# CAMAC.net
KiCad netlist of a schematic drawn in Altium Designer
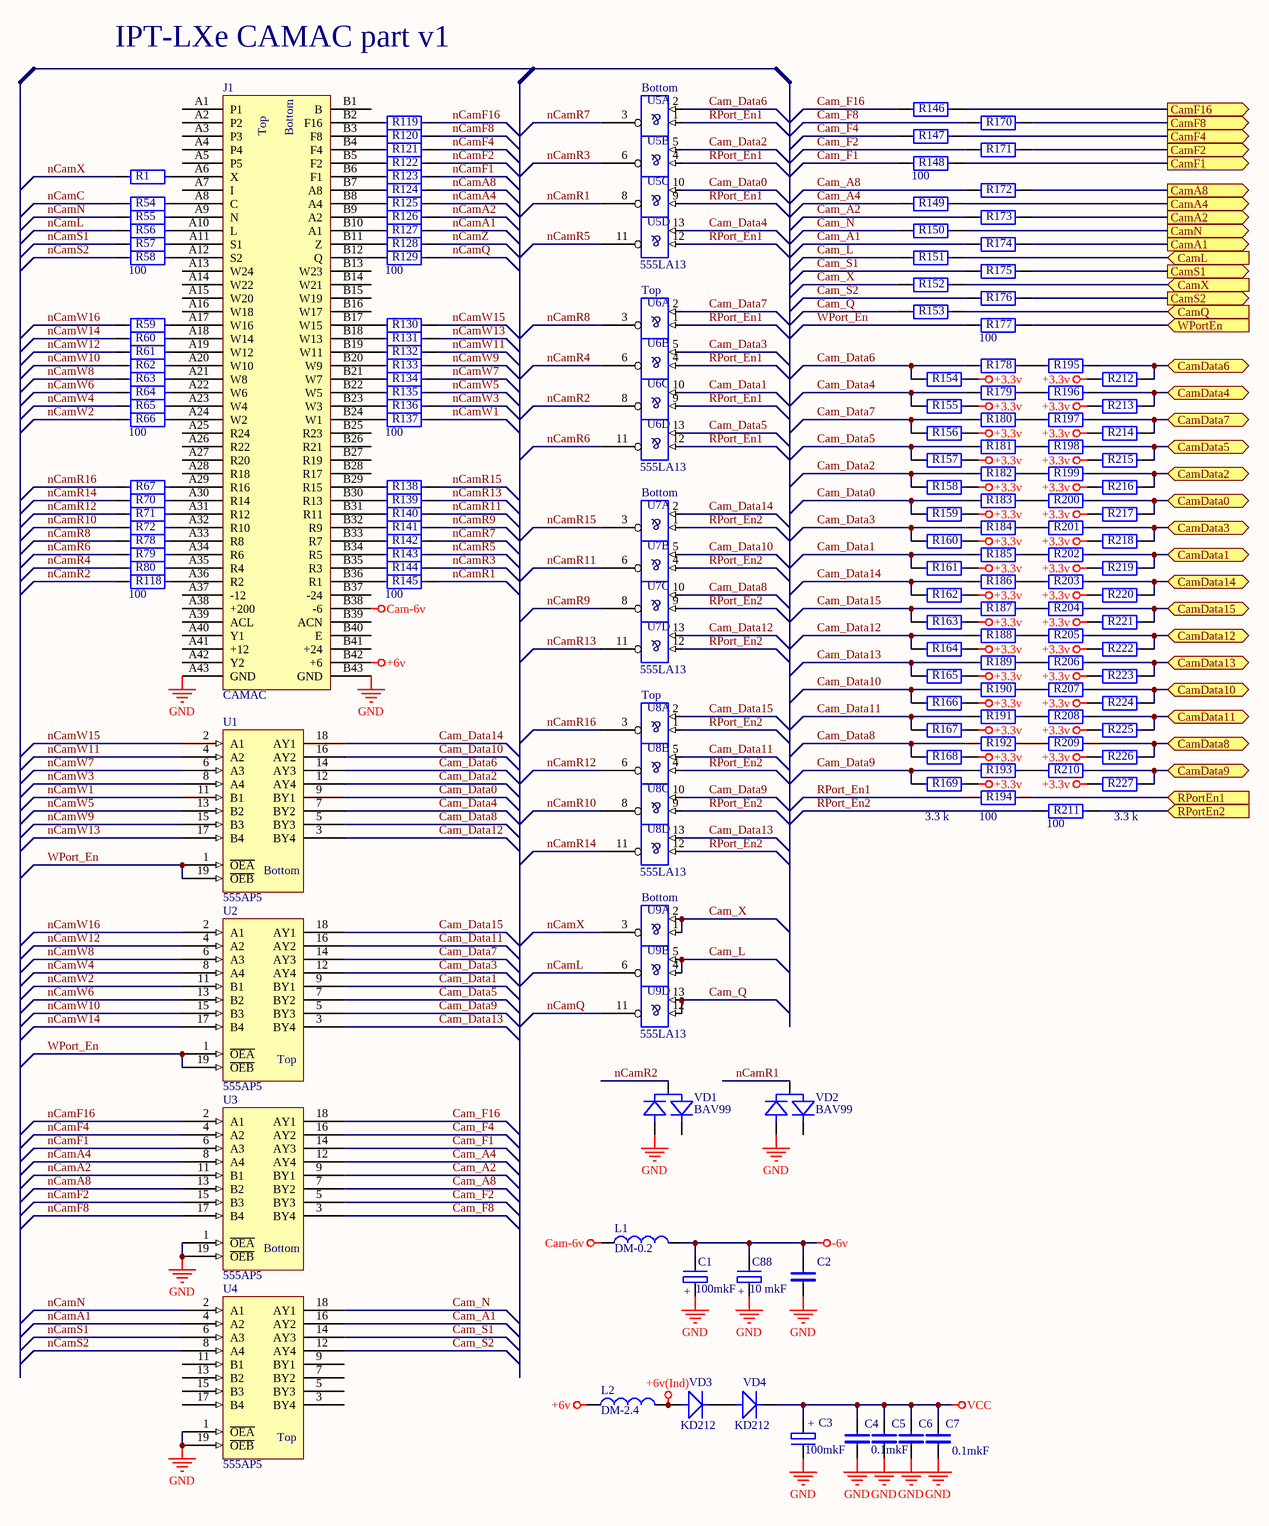
[diagram p0: CAMAC.SchDoc]

(export (version "E")
  (design (tool "Eeschema 10.0.6"))
  (components
    (comp (ref "C1") (value "100mkF") (footprint "CP7343") (libsource (lib "*") (part "C POL")))
    (comp (ref "C2") (value "0.1mkF") (footprint "chip1206") (libsource (lib "vDevice") (part "C")))
    (comp (ref "C3") (value "100mkF") (footprint "CP7343") (libsource (lib "*") (part "C POL")))
    (comp (ref "C4") (value "0.1mkF") (footprint "chip1206") (libsource (lib "vDevice") (part "C")))
    (comp (ref "C5") (value "0.1mkF") (footprint "chip1206") (libsource (lib "vDevice") (part "C")))
    (comp (ref "C6") (value "0.1mkF") (footprint "chip1206") (libsource (lib "vDevice") (part "C")))
    (comp (ref "C7") (value "0.1mkF") (footprint "chip1206") (libsource (lib "vDevice") (part "C")))
    (comp (ref "C88") (value "10 mkF") (footprint "CP6032") (libsource (lib "*") (part "C POL")))
    (comp (ref "J1") (value "CAMAC") (footprint "CAMAC") (libsource (lib "*") (part "CAMACF")))
    (comp (ref "L1") (value "DM-0.2") (footprint "INDUCT2") (libsource (lib "*") (part "INDUCTOR")))
    (comp (ref "L2") (value "DM-2.4") (footprint "INDUCT2") (libsource (lib "*") (part "INDUCTOR")))
    (comp (ref "R1") (value "100") (footprint "chip0805") (libsource (lib "vDevice") (part "R")))
    (comp (ref "R54") (value "100") (footprint "chip0805") (libsource (lib "vDevice") (part "R")))
    (comp (ref "R55") (value "100") (footprint "chip0805") (libsource (lib "vDevice") (part "R")))
    (comp (ref "R56") (value "100") (footprint "chip0805") (libsource (lib "vDevice") (part "R")))
    (comp (ref "R57") (value "100") (footprint "chip0805") (libsource (lib "vDevice") (part "R")))
    (comp (ref "R58") (value "100") (footprint "chip0805") (libsource (lib "vDevice") (part "R")))
    (comp (ref "R59") (value "100") (footprint "chip0805") (libsource (lib "vDevice") (part "R")))
    (comp (ref "R60") (value "100") (footprint "chip0805") (libsource (lib "vDevice") (part "R")))
    (comp (ref "R61") (value "100") (footprint "chip0805") (libsource (lib "vDevice") (part "R")))
    (comp (ref "R62") (value "100") (footprint "chip0805") (libsource (lib "vDevice") (part "R")))
    (comp (ref "R63") (value "100") (footprint "chip0805") (libsource (lib "vDevice") (part "R")))
    (comp (ref "R64") (value "100") (footprint "chip0805") (libsource (lib "vDevice") (part "R")))
    (comp (ref "R65") (value "100") (footprint "chip0805") (libsource (lib "vDevice") (part "R")))
    (comp (ref "R66") (value "100") (footprint "chip0805") (libsource (lib "vDevice") (part "R")))
    (comp (ref "R67") (value "100") (footprint "chip0805") (libsource (lib "vDevice") (part "R")))
    (comp (ref "R70") (value "100") (footprint "chip0805") (libsource (lib "vDevice") (part "R")))
    (comp (ref "R71") (value "100") (footprint "chip0805") (libsource (lib "vDevice") (part "R")))
    (comp (ref "R72") (value "100") (footprint "chip0805") (libsource (lib "vDevice") (part "R")))
    (comp (ref "R78") (value "100") (footprint "chip0805") (libsource (lib "vDevice") (part "R")))
    (comp (ref "R79") (value "100") (footprint "chip0805") (libsource (lib "vDevice") (part "R")))
    (comp (ref "R80") (value "100") (footprint "chip0805") (libsource (lib "vDevice") (part "R")))
    (comp (ref "R118") (value "100") (footprint "chip0805") (libsource (lib "vDevice") (part "R")))
    (comp (ref "R119") (value "100") (footprint "chip0805") (libsource (lib "vDevice") (part "R")))
    (comp (ref "R120") (value "100") (footprint "chip0805") (libsource (lib "vDevice") (part "R")))
    (comp (ref "R121") (value "100") (footprint "chip0805") (libsource (lib "vDevice") (part "R")))
    (comp (ref "R122") (value "100") (footprint "chip0805") (libsource (lib "vDevice") (part "R")))
    (comp (ref "R123") (value "100") (footprint "chip0805") (libsource (lib "vDevice") (part "R")))
    (comp (ref "R124") (value "100") (footprint "chip0805") (libsource (lib "vDevice") (part "R")))
    (comp (ref "R125") (value "100") (footprint "chip0805") (libsource (lib "vDevice") (part "R")))
    (comp (ref "R126") (value "100") (footprint "chip0805") (libsource (lib "vDevice") (part "R")))
    (comp (ref "R127") (value "100") (footprint "chip0805") (libsource (lib "vDevice") (part "R")))
    (comp (ref "R128") (value "100") (footprint "chip0805") (libsource (lib "vDevice") (part "R")))
    (comp (ref "R129") (value "100") (footprint "chip0805") (libsource (lib "vDevice") (part "R")))
    (comp (ref "R130") (value "100") (footprint "chip0805") (libsource (lib "vDevice") (part "R")))
    (comp (ref "R131") (value "100") (footprint "chip0805") (libsource (lib "vDevice") (part "R")))
    (comp (ref "R132") (value "100") (footprint "chip0805") (libsource (lib "vDevice") (part "R")))
    (comp (ref "R133") (value "100") (footprint "chip0805") (libsource (lib "vDevice") (part "R")))
    (comp (ref "R134") (value "100") (footprint "chip0805") (libsource (lib "vDevice") (part "R")))
    (comp (ref "R135") (value "100") (footprint "chip0805") (libsource (lib "vDevice") (part "R")))
    (comp (ref "R136") (value "100") (footprint "chip0805") (libsource (lib "vDevice") (part "R")))
    (comp (ref "R137") (value "100") (footprint "chip0805") (libsource (lib "vDevice") (part "R")))
    (comp (ref "R138") (value "100") (footprint "chip0805") (libsource (lib "vDevice") (part "R")))
    (comp (ref "R139") (value "100") (footprint "chip0805") (libsource (lib "vDevice") (part "R")))
    (comp (ref "R140") (value "100") (footprint "chip0805") (libsource (lib "vDevice") (part "R")))
    (comp (ref "R141") (value "100") (footprint "chip0805") (libsource (lib "vDevice") (part "R")))
    (comp (ref "R142") (value "100") (footprint "chip0805") (libsource (lib "vDevice") (part "R")))
    (comp (ref "R143") (value "100") (footprint "chip0805") (libsource (lib "vDevice") (part "R")))
    (comp (ref "R144") (value "100") (footprint "chip0805") (libsource (lib "vDevice") (part "R")))
    (comp (ref "R145") (value "100") (footprint "chip0805") (libsource (lib "vDevice") (part "R")))
    (comp (ref "R146") (value "100") (footprint "chip0805") (libsource (lib "vDevice") (part "R")))
    (comp (ref "R147") (value "100") (footprint "chip0805") (libsource (lib "vDevice") (part "R")))
    (comp (ref "R148") (value "100") (footprint "chip0805") (libsource (lib "vDevice") (part "R")))
    (comp (ref "R149") (value "100") (footprint "chip0805") (libsource (lib "vDevice") (part "R")))
    (comp (ref "R150") (value "100") (footprint "chip0805") (libsource (lib "vDevice") (part "R")))
    (comp (ref "R151") (value "100") (footprint "chip0805") (libsource (lib "vDevice") (part "R")))
    (comp (ref "R152") (value "100") (footprint "chip0805") (libsource (lib "vDevice") (part "R")))
    (comp (ref "R153") (value "100") (footprint "chip0805") (libsource (lib "vDevice") (part "R")))
    (comp (ref "R154") (value "3.3 k") (footprint "chip0805") (libsource (lib "vDevice") (part "R")))
    (comp (ref "R155") (value "3.3 k") (footprint "chip0805") (libsource (lib "vDevice") (part "R")))
    (comp (ref "R156") (value "3.3 k") (footprint "chip0805") (libsource (lib "vDevice") (part "R")))
    (comp (ref "R157") (value "3.3 k") (footprint "chip0805") (libsource (lib "vDevice") (part "R")))
    (comp (ref "R158") (value "3.3 k") (footprint "chip0805") (libsource (lib "vDevice") (part "R")))
    (comp (ref "R159") (value "3.3 k") (footprint "chip0805") (libsource (lib "vDevice") (part "R")))
    (comp (ref "R160") (value "3.3 k") (footprint "chip0805") (libsource (lib "vDevice") (part "R")))
    (comp (ref "R161") (value "3.3 k") (footprint "chip0805") (libsource (lib "vDevice") (part "R")))
    (comp (ref "R162") (value "3.3 k") (footprint "chip0805") (libsource (lib "vDevice") (part "R")))
    (comp (ref "R163") (value "3.3 k") (footprint "chip0805") (libsource (lib "vDevice") (part "R")))
    (comp (ref "R164") (value "3.3 k") (footprint "chip0805") (libsource (lib "vDevice") (part "R")))
    (comp (ref "R165") (value "3.3 k") (footprint "chip0805") (libsource (lib "vDevice") (part "R")))
    (comp (ref "R166") (value "3.3 k") (footprint "chip0805") (libsource (lib "vDevice") (part "R")))
    (comp (ref "R167") (value "3.3 k") (footprint "chip0805") (libsource (lib "vDevice") (part "R")))
    (comp (ref "R168") (value "3.3 k") (footprint "chip0805") (libsource (lib "vDevice") (part "R")))
    (comp (ref "R169") (value "3.3 k") (footprint "chip0805") (libsource (lib "vDevice") (part "R")))
    (comp (ref "R170") (value "100") (footprint "chip0805") (libsource (lib "vDevice") (part "R")))
    (comp (ref "R171") (value "100") (footprint "chip0805") (libsource (lib "vDevice") (part "R")))
    (comp (ref "R172") (value "100") (footprint "chip0805") (libsource (lib "vDevice") (part "R")))
    (comp (ref "R173") (value "100") (footprint "chip0805") (libsource (lib "vDevice") (part "R")))
    (comp (ref "R174") (value "100") (footprint "chip0805") (libsource (lib "vDevice") (part "R")))
    (comp (ref "R175") (value "100") (footprint "chip0805") (libsource (lib "vDevice") (part "R")))
    (comp (ref "R176") (value "100") (footprint "chip0805") (libsource (lib "vDevice") (part "R")))
    (comp (ref "R177") (value "100") (footprint "chip0805") (libsource (lib "vDevice") (part "R")))
    (comp (ref "R178") (value "51") (footprint "chip0805") (libsource (lib "vDevice") (part "R")))
    (comp (ref "R179") (value "51") (footprint "chip0805") (libsource (lib "vDevice") (part "R")))
    (comp (ref "R180") (value "51") (footprint "chip0805") (libsource (lib "vDevice") (part "R")))
    (comp (ref "R181") (value "51") (footprint "chip0805") (libsource (lib "vDevice") (part "R")))
    (comp (ref "R182") (value "51") (footprint "chip0805") (libsource (lib "vDevice") (part "R")))
    (comp (ref "R183") (value "51") (footprint "chip0805") (libsource (lib "vDevice") (part "R")))
    (comp (ref "R184") (value "51") (footprint "chip0805") (libsource (lib "vDevice") (part "R")))
    (comp (ref "R185") (value "51") (footprint "chip0805") (libsource (lib "vDevice") (part "R")))
    (comp (ref "R186") (value "51") (footprint "chip0805") (libsource (lib "vDevice") (part "R")))
    (comp (ref "R187") (value "51") (footprint "chip0805") (libsource (lib "vDevice") (part "R")))
    (comp (ref "R188") (value "51") (footprint "chip0805") (libsource (lib "vDevice") (part "R")))
    (comp (ref "R189") (value "51") (footprint "chip0805") (libsource (lib "vDevice") (part "R")))
    (comp (ref "R190") (value "51") (footprint "chip0805") (libsource (lib "vDevice") (part "R")))
    (comp (ref "R191") (value "51") (footprint "chip0805") (libsource (lib "vDevice") (part "R")))
    (comp (ref "R192") (value "51") (footprint "chip0805") (libsource (lib "vDevice") (part "R")))
    (comp (ref "R193") (value "51") (footprint "chip0805") (libsource (lib "vDevice") (part "R")))
    (comp (ref "R194") (value "100") (footprint "chip0805") (libsource (lib "vDevice") (part "R")))
    (comp (ref "R195") (value "51") (footprint "chip0805") (libsource (lib "vDevice") (part "R")))
    (comp (ref "R196") (value "51") (footprint "chip0805") (libsource (lib "vDevice") (part "R")))
    (comp (ref "R197") (value "51") (footprint "chip0805") (libsource (lib "vDevice") (part "R")))
    (comp (ref "R198") (value "51") (footprint "chip0805") (libsource (lib "vDevice") (part "R")))
    (comp (ref "R199") (value "51") (footprint "chip0805") (libsource (lib "vDevice") (part "R")))
    (comp (ref "R200") (value "51") (footprint "chip0805") (libsource (lib "vDevice") (part "R")))
    (comp (ref "R201") (value "51") (footprint "chip0805") (libsource (lib "vDevice") (part "R")))
    (comp (ref "R202") (value "51") (footprint "chip0805") (libsource (lib "vDevice") (part "R")))
    (comp (ref "R203") (value "51") (footprint "chip0805") (libsource (lib "vDevice") (part "R")))
    (comp (ref "R204") (value "51") (footprint "chip0805") (libsource (lib "vDevice") (part "R")))
    (comp (ref "R205") (value "51") (footprint "chip0805") (libsource (lib "vDevice") (part "R")))
    (comp (ref "R206") (value "51") (footprint "chip0805") (libsource (lib "vDevice") (part "R")))
    (comp (ref "R207") (value "51") (footprint "chip0805") (libsource (lib "vDevice") (part "R")))
    (comp (ref "R208") (value "51") (footprint "chip0805") (libsource (lib "vDevice") (part "R")))
    (comp (ref "R209") (value "51") (footprint "chip0805") (libsource (lib "vDevice") (part "R")))
    (comp (ref "R210") (value "51") (footprint "chip0805") (libsource (lib "vDevice") (part "R")))
    (comp (ref "R211") (value "100") (footprint "chip0805") (libsource (lib "vDevice") (part "R")))
    (comp (ref "R212") (value "3.3 k") (footprint "chip0805") (libsource (lib "vDevice") (part "R")))
    (comp (ref "R213") (value "3.3 k") (footprint "chip0805") (libsource (lib "vDevice") (part "R")))
    (comp (ref "R214") (value "3.3 k") (footprint "chip0805") (libsource (lib "vDevice") (part "R")))
    (comp (ref "R215") (value "3.3 k") (footprint "chip0805") (libsource (lib "vDevice") (part "R")))
    (comp (ref "R216") (value "3.3 k") (footprint "chip0805") (libsource (lib "vDevice") (part "R")))
    (comp (ref "R217") (value "3.3 k") (footprint "chip0805") (libsource (lib "vDevice") (part "R")))
    (comp (ref "R218") (value "3.3 k") (footprint "chip0805") (libsource (lib "vDevice") (part "R")))
    (comp (ref "R219") (value "3.3 k") (footprint "chip0805") (libsource (lib "vDevice") (part "R")))
    (comp (ref "R220") (value "3.3 k") (footprint "chip0805") (libsource (lib "vDevice") (part "R")))
    (comp (ref "R221") (value "3.3 k") (footprint "chip0805") (libsource (lib "vDevice") (part "R")))
    (comp (ref "R222") (value "3.3 k") (footprint "chip0805") (libsource (lib "vDevice") (part "R")))
    (comp (ref "R223") (value "3.3 k") (footprint "chip0805") (libsource (lib "vDevice") (part "R")))
    (comp (ref "R224") (value "3.3 k") (footprint "chip0805") (libsource (lib "vDevice") (part "R")))
    (comp (ref "R225") (value "3.3 k") (footprint "chip0805") (libsource (lib "vDevice") (part "R")))
    (comp (ref "R226") (value "3.3 k") (footprint "chip0805") (libsource (lib "vDevice") (part "R")))
    (comp (ref "R227") (value "3.3 k") (footprint "chip0805") (libsource (lib "vDevice") (part "R")))
    (comp (ref "U1") (value "555AP5") (libsource (lib "vTTL") (part "555AP5")))
    (comp (ref "U2") (value "555AP5") (libsource (lib "vTTL") (part "555AP5")))
    (comp (ref "U3") (value "555AP5") (libsource (lib "vTTL") (part "555AP5")))
    (comp (ref "U4") (value "555AP5") (libsource (lib "vTTL") (part "555AP5")))
    (comp (ref "U5") (value "555LA13") (footprint "14DIP300") (libsource (lib "vTTL") (part "555LA13")))
    (comp (ref "U6") (value "555LA13") (footprint "14DIP300") (libsource (lib "vTTL") (part "555LA13")))
    (comp (ref "U7") (value "555LA13") (footprint "14DIP300") (libsource (lib "vTTL") (part "555LA13")))
    (comp (ref "U8") (value "555LA13") (footprint "14DIP300") (libsource (lib "vTTL") (part "555LA13")))
    (comp (ref "U9") (value "555LA13") (footprint "14DIP300") (libsource (lib "vTTL") (part "555LA13")))
    (comp (ref "VD1")
      (value "BAV99")
      (footprint "SOT-23")
      (description "Double diode")
      (libsource (lib "*") (part "BAV99"))
    )
    (comp (ref "VD2")
      (value "BAV99")
      (footprint "SOT-23")
      (description "Double diode")
      (libsource (lib "*") (part "BAV99"))
    )
    (comp (ref "VD3") (value "KD212") (footprint "DIODE6") (libsource (lib "*") (part "AD110")))
    (comp (ref "VD4") (value "KD212") (footprint "DIODE6") (libsource (lib "*") (part "AD110")))
  )
  (nets
    (net (code "1") (name "+3.3v") (class "Default")
      (node (ref "R154") (pin "2") (pinfunction "2_2") (pintype "passive"))
      (node (ref "R155") (pin "2") (pinfunction "2_2") (pintype "passive"))
      (node (ref "R156") (pin "2") (pinfunction "2_2") (pintype "passive"))
      (node (ref "R157") (pin "2") (pinfunction "2_2") (pintype "passive"))
      (node (ref "R158") (pin "2") (pinfunction "2_2") (pintype "passive"))
      (node (ref "R159") (pin "2") (pinfunction "2_2") (pintype "passive"))
      (node (ref "R160") (pin "2") (pinfunction "2_2") (pintype "passive"))
      (node (ref "R161") (pin "2") (pinfunction "2_2") (pintype "passive"))
      (node (ref "R162") (pin "2") (pinfunction "2_2") (pintype "passive"))
      (node (ref "R163") (pin "2") (pinfunction "2_2") (pintype "passive"))
      (node (ref "R164") (pin "2") (pinfunction "2_2") (pintype "passive"))
      (node (ref "R165") (pin "2") (pinfunction "2_2") (pintype "passive"))
      (node (ref "R166") (pin "2") (pinfunction "2_2") (pintype "passive"))
      (node (ref "R167") (pin "2") (pinfunction "2_2") (pintype "passive"))
      (node (ref "R168") (pin "2") (pinfunction "2_2") (pintype "passive"))
      (node (ref "R169") (pin "2") (pinfunction "2_2") (pintype "passive"))
      (node (ref "R212") (pin "1") (pinfunction "1_1") (pintype "passive"))
      (node (ref "R213") (pin "1") (pinfunction "1_1") (pintype "passive"))
      (node (ref "R214") (pin "1") (pinfunction "1_1") (pintype "passive"))
      (node (ref "R215") (pin "1") (pinfunction "1_1") (pintype "passive"))
      (node (ref "R216") (pin "1") (pinfunction "1_1") (pintype "passive"))
      (node (ref "R217") (pin "1") (pinfunction "1_1") (pintype "passive"))
      (node (ref "R218") (pin "1") (pinfunction "1_1") (pintype "passive"))
      (node (ref "R219") (pin "1") (pinfunction "1_1") (pintype "passive"))
      (node (ref "R220") (pin "1") (pinfunction "1_1") (pintype "passive"))
      (node (ref "R221") (pin "1") (pinfunction "1_1") (pintype "passive"))
      (node (ref "R222") (pin "1") (pinfunction "1_1") (pintype "passive"))
      (node (ref "R223") (pin "1") (pinfunction "1_1") (pintype "passive"))
      (node (ref "R224") (pin "1") (pinfunction "1_1") (pintype "passive"))
      (node (ref "R225") (pin "1") (pinfunction "1_1") (pintype "passive"))
      (node (ref "R226") (pin "1") (pinfunction "1_1") (pintype "passive"))
      (node (ref "R227") (pin "1") (pinfunction "1_1") (pintype "passive"))
    )
    (net (code "2") (name "+5V") (class "Default")
      (node (ref "U1") (pin "20") (pinfunction "+5V_20") (pintype "power_in"))
      (node (ref "U2") (pin "20") (pinfunction "+5V_20") (pintype "power_in"))
      (node (ref "U3") (pin "20") (pinfunction "+5V_20") (pintype "power_in"))
      (node (ref "U4") (pin "20") (pinfunction "+5V_20") (pintype "power_in"))
    )
    (net (code "3") (name "+6v") (class "Default")
      (node (ref "J1") (pin "B42") (pinfunction "+6_B42") (pintype "passive"))
      (node (ref "L2") (pin "1") (pinfunction "1_1") (pintype "passive"))
    )
    (net (code "4") (name "+6v(Ind)") (class "Default")
      (node (ref "L2") (pin "2") (pinfunction "2_2") (pintype "passive"))
      (node (ref "VD3") (pin "ANOD") (pinfunction "ANOD_ANOD") (pintype "passive"))
    )
    (net (code "5") (name "-6v") (class "Default")
      (node (ref "C1") (pin "-") (pinfunction "-_-") (pintype "passive"))
      (node (ref "C2") (pin "1") (pinfunction "1_1") (pintype "passive"))
      (node (ref "C88") (pin "-") (pinfunction "-_-") (pintype "passive"))
      (node (ref "L1") (pin "2") (pinfunction "2_2") (pintype "passive"))
    )
    (net (code "6") (name "/CamA1") (class "Default")
      (node (ref "R174") (pin "2") (pinfunction "2_2") (pintype "passive"))
    )
    (net (code "7") (name "/CamA2") (class "Default")
      (node (ref "R173") (pin "2") (pinfunction "2_2") (pintype "passive"))
    )
    (net (code "8") (name "/CamA4") (class "Default")
      (node (ref "R149") (pin "2") (pinfunction "2_2") (pintype "passive"))
    )
    (net (code "9") (name "/CamA8") (class "Default")
      (node (ref "R172") (pin "2") (pinfunction "2_2") (pintype "passive"))
    )
    (net (code "10") (name "/CamData0") (class "Default")
      (node (ref "R200") (pin "2") (pinfunction "2_2") (pintype "passive"))
      (node (ref "R217") (pin "2") (pinfunction "2_2") (pintype "passive"))
    )
    (net (code "11") (name "/CamData1") (class "Default")
      (node (ref "R202") (pin "2") (pinfunction "2_2") (pintype "passive"))
      (node (ref "R219") (pin "2") (pinfunction "2_2") (pintype "passive"))
    )
    (net (code "12") (name "/CamData2") (class "Default")
      (node (ref "R199") (pin "2") (pinfunction "2_2") (pintype "passive"))
      (node (ref "R216") (pin "2") (pinfunction "2_2") (pintype "passive"))
    )
    (net (code "13") (name "/CamData3") (class "Default")
      (node (ref "R201") (pin "2") (pinfunction "2_2") (pintype "passive"))
      (node (ref "R218") (pin "2") (pinfunction "2_2") (pintype "passive"))
    )
    (net (code "14") (name "/CamData4") (class "Default")
      (node (ref "R196") (pin "2") (pinfunction "2_2") (pintype "passive"))
      (node (ref "R213") (pin "2") (pinfunction "2_2") (pintype "passive"))
    )
    (net (code "15") (name "/CamData5") (class "Default")
      (node (ref "R198") (pin "2") (pinfunction "2_2") (pintype "passive"))
      (node (ref "R215") (pin "2") (pinfunction "2_2") (pintype "passive"))
    )
    (net (code "16") (name "/CamData6") (class "Default")
      (node (ref "R195") (pin "2") (pinfunction "2_2") (pintype "passive"))
      (node (ref "R212") (pin "2") (pinfunction "2_2") (pintype "passive"))
    )
    (net (code "17") (name "/CamData7") (class "Default")
      (node (ref "R197") (pin "2") (pinfunction "2_2") (pintype "passive"))
      (node (ref "R214") (pin "2") (pinfunction "2_2") (pintype "passive"))
    )
    (net (code "18") (name "/CamData8") (class "Default")
      (node (ref "R209") (pin "2") (pinfunction "2_2") (pintype "passive"))
      (node (ref "R226") (pin "2") (pinfunction "2_2") (pintype "passive"))
    )
    (net (code "19") (name "/CamData9") (class "Default")
      (node (ref "R210") (pin "2") (pinfunction "2_2") (pintype "passive"))
      (node (ref "R227") (pin "2") (pinfunction "2_2") (pintype "passive"))
    )
    (net (code "20") (name "/CamData10") (class "Default")
      (node (ref "R207") (pin "2") (pinfunction "2_2") (pintype "passive"))
      (node (ref "R224") (pin "2") (pinfunction "2_2") (pintype "passive"))
    )
    (net (code "21") (name "/CamData11") (class "Default")
      (node (ref "R208") (pin "2") (pinfunction "2_2") (pintype "passive"))
      (node (ref "R225") (pin "2") (pinfunction "2_2") (pintype "passive"))
    )
    (net (code "22") (name "/CamData12") (class "Default")
      (node (ref "R205") (pin "2") (pinfunction "2_2") (pintype "passive"))
      (node (ref "R222") (pin "2") (pinfunction "2_2") (pintype "passive"))
    )
    (net (code "23") (name "/CamData13") (class "Default")
      (node (ref "R206") (pin "2") (pinfunction "2_2") (pintype "passive"))
      (node (ref "R223") (pin "2") (pinfunction "2_2") (pintype "passive"))
    )
    (net (code "24") (name "/CamData14") (class "Default")
      (node (ref "R203") (pin "2") (pinfunction "2_2") (pintype "passive"))
      (node (ref "R220") (pin "2") (pinfunction "2_2") (pintype "passive"))
    )
    (net (code "25") (name "/CamData15") (class "Default")
      (node (ref "R204") (pin "2") (pinfunction "2_2") (pintype "passive"))
      (node (ref "R221") (pin "2") (pinfunction "2_2") (pintype "passive"))
    )
    (net (code "26") (name "/CamF1") (class "Default")
      (node (ref "R148") (pin "2") (pinfunction "2_2") (pintype "passive"))
    )
    (net (code "27") (name "/CamF2") (class "Default")
      (node (ref "R171") (pin "2") (pinfunction "2_2") (pintype "passive"))
    )
    (net (code "28") (name "/CamF4") (class "Default")
      (node (ref "R147") (pin "2") (pinfunction "2_2") (pintype "passive"))
    )
    (net (code "29") (name "/CamF8") (class "Default")
      (node (ref "R170") (pin "2") (pinfunction "2_2") (pintype "passive"))
    )
    (net (code "30") (name "/CamF16") (class "Default")
      (node (ref "R146") (pin "2") (pinfunction "2_2") (pintype "passive"))
    )
    (net (code "31") (name "/CamL") (class "Default")
      (node (ref "R151") (pin "2") (pinfunction "2_2") (pintype "passive"))
    )
    (net (code "32") (name "/CamN") (class "Default")
      (node (ref "R150") (pin "2") (pinfunction "2_2") (pintype "passive"))
    )
    (net (code "33") (name "/CamQ") (class "Default")
      (node (ref "R153") (pin "2") (pinfunction "2_2") (pintype "passive"))
    )
    (net (code "34") (name "/CamS1") (class "Default")
      (node (ref "R175") (pin "2") (pinfunction "2_2") (pintype "passive"))
    )
    (net (code "35") (name "/CamS2") (class "Default")
      (node (ref "R176") (pin "2") (pinfunction "2_2") (pintype "passive"))
    )
    (net (code "36") (name "/CamX") (class "Default")
      (node (ref "R152") (pin "2") (pinfunction "2_2") (pintype "passive"))
    )
    (net (code "37") (name "/Cam_A1") (class "Default")
      (node (ref "R174") (pin "1") (pinfunction "1_1") (pintype "passive"))
      (node (ref "U4") (pin "16") (pinfunction "AY2_16") (pintype "tri_state"))
    )
    (net (code "38") (name "/Cam_A2") (class "Default")
      (node (ref "R173") (pin "1") (pinfunction "1_1") (pintype "passive"))
      (node (ref "U3") (pin "9") (pinfunction "BY1_9") (pintype "tri_state"))
    )
    (net (code "39") (name "/Cam_A4") (class "Default")
      (node (ref "R149") (pin "1") (pinfunction "1_1") (pintype "passive"))
      (node (ref "U3") (pin "12") (pinfunction "AY4_12") (pintype "tri_state"))
    )
    (net (code "40") (name "/Cam_A8") (class "Default")
      (node (ref "R172") (pin "1") (pinfunction "1_1") (pintype "passive"))
      (node (ref "U3") (pin "7") (pinfunction "BY2_7") (pintype "tri_state"))
    )
    (net (code "41") (name "/Cam_Data0") (class "Default")
      (node (ref "R159") (pin "1") (pinfunction "1_1") (pintype "passive"))
      (node (ref "R183") (pin "1") (pinfunction "1_1") (pintype "passive"))
      (node (ref "U1") (pin "9") (pinfunction "BY1_9") (pintype "tri_state"))
      (node (ref "U5") (pin "10") (pinfunction "I1_10") (pintype "input"))
    )
    (net (code "42") (name "/Cam_Data1") (class "Default")
      (node (ref "R161") (pin "1") (pinfunction "1_1") (pintype "passive"))
      (node (ref "R185") (pin "1") (pinfunction "1_1") (pintype "passive"))
      (node (ref "U2") (pin "9") (pinfunction "BY1_9") (pintype "tri_state"))
      (node (ref "U6") (pin "10") (pinfunction "I1_10") (pintype "input"))
    )
    (net (code "43") (name "/Cam_Data2") (class "Default")
      (node (ref "R158") (pin "1") (pinfunction "1_1") (pintype "passive"))
      (node (ref "R182") (pin "1") (pinfunction "1_1") (pintype "passive"))
      (node (ref "U1") (pin "12") (pinfunction "AY4_12") (pintype "tri_state"))
      (node (ref "U5") (pin "5") (pinfunction "I1_5") (pintype "input"))
    )
    (net (code "44") (name "/Cam_Data3") (class "Default")
      (node (ref "R160") (pin "1") (pinfunction "1_1") (pintype "passive"))
      (node (ref "R184") (pin "1") (pinfunction "1_1") (pintype "passive"))
      (node (ref "U2") (pin "12") (pinfunction "AY4_12") (pintype "tri_state"))
      (node (ref "U6") (pin "5") (pinfunction "I1_5") (pintype "input"))
    )
    (net (code "45") (name "/Cam_Data4") (class "Default")
      (node (ref "R155") (pin "1") (pinfunction "1_1") (pintype "passive"))
      (node (ref "R179") (pin "1") (pinfunction "1_1") (pintype "passive"))
      (node (ref "U1") (pin "7") (pinfunction "BY2_7") (pintype "tri_state"))
      (node (ref "U5") (pin "13") (pinfunction "I1_13") (pintype "input"))
    )
    (net (code "46") (name "/Cam_Data5") (class "Default")
      (node (ref "R157") (pin "1") (pinfunction "1_1") (pintype "passive"))
      (node (ref "R181") (pin "1") (pinfunction "1_1") (pintype "passive"))
      (node (ref "U2") (pin "7") (pinfunction "BY2_7") (pintype "tri_state"))
      (node (ref "U6") (pin "13") (pinfunction "I1_13") (pintype "input"))
    )
    (net (code "47") (name "/Cam_Data6") (class "Default")
      (node (ref "R154") (pin "1") (pinfunction "1_1") (pintype "passive"))
      (node (ref "R178") (pin "1") (pinfunction "1_1") (pintype "passive"))
      (node (ref "U1") (pin "14") (pinfunction "AY3_14") (pintype "tri_state"))
      (node (ref "U5") (pin "2") (pinfunction "I1_2") (pintype "input"))
    )
    (net (code "48") (name "/Cam_Data7") (class "Default")
      (node (ref "R156") (pin "1") (pinfunction "1_1") (pintype "passive"))
      (node (ref "R180") (pin "1") (pinfunction "1_1") (pintype "passive"))
      (node (ref "U2") (pin "14") (pinfunction "AY3_14") (pintype "tri_state"))
      (node (ref "U6") (pin "2") (pinfunction "I1_2") (pintype "input"))
    )
    (net (code "49") (name "/Cam_Data8") (class "Default")
      (node (ref "R168") (pin "1") (pinfunction "1_1") (pintype "passive"))
      (node (ref "R192") (pin "1") (pinfunction "1_1") (pintype "passive"))
      (node (ref "U1") (pin "5") (pinfunction "BY3_5") (pintype "tri_state"))
      (node (ref "U7") (pin "10") (pinfunction "I1_10") (pintype "input"))
    )
    (net (code "50") (name "/Cam_Data9") (class "Default")
      (node (ref "R169") (pin "1") (pinfunction "1_1") (pintype "passive"))
      (node (ref "R193") (pin "1") (pinfunction "1_1") (pintype "passive"))
      (node (ref "U2") (pin "5") (pinfunction "BY3_5") (pintype "tri_state"))
      (node (ref "U8") (pin "10") (pinfunction "I1_10") (pintype "input"))
    )
    (net (code "51") (name "/Cam_Data10") (class "Default")
      (node (ref "R166") (pin "1") (pinfunction "1_1") (pintype "passive"))
      (node (ref "R190") (pin "1") (pinfunction "1_1") (pintype "passive"))
      (node (ref "U1") (pin "16") (pinfunction "AY2_16") (pintype "tri_state"))
      (node (ref "U7") (pin "5") (pinfunction "I1_5") (pintype "input"))
    )
    (net (code "52") (name "/Cam_Data11") (class "Default")
      (node (ref "R167") (pin "1") (pinfunction "1_1") (pintype "passive"))
      (node (ref "R191") (pin "1") (pinfunction "1_1") (pintype "passive"))
      (node (ref "U2") (pin "16") (pinfunction "AY2_16") (pintype "tri_state"))
      (node (ref "U8") (pin "5") (pinfunction "I1_5") (pintype "input"))
    )
    (net (code "53") (name "/Cam_Data12") (class "Default")
      (node (ref "R164") (pin "1") (pinfunction "1_1") (pintype "passive"))
      (node (ref "R188") (pin "1") (pinfunction "1_1") (pintype "passive"))
      (node (ref "U1") (pin "3") (pinfunction "BY4_3") (pintype "tri_state"))
      (node (ref "U7") (pin "13") (pinfunction "I1_13") (pintype "input"))
    )
    (net (code "54") (name "/Cam_Data13") (class "Default")
      (node (ref "R165") (pin "1") (pinfunction "1_1") (pintype "passive"))
      (node (ref "R189") (pin "1") (pinfunction "1_1") (pintype "passive"))
      (node (ref "U2") (pin "3") (pinfunction "BY4_3") (pintype "tri_state"))
      (node (ref "U8") (pin "13") (pinfunction "I1_13") (pintype "input"))
    )
    (net (code "55") (name "/Cam_Data14") (class "Default")
      (node (ref "R162") (pin "1") (pinfunction "1_1") (pintype "passive"))
      (node (ref "R186") (pin "1") (pinfunction "1_1") (pintype "passive"))
      (node (ref "U1") (pin "18") (pinfunction "AY1_18") (pintype "tri_state"))
      (node (ref "U7") (pin "2") (pinfunction "I1_2") (pintype "input"))
    )
    (net (code "56") (name "/Cam_Data15") (class "Default")
      (node (ref "R163") (pin "1") (pinfunction "1_1") (pintype "passive"))
      (node (ref "R187") (pin "1") (pinfunction "1_1") (pintype "passive"))
      (node (ref "U2") (pin "18") (pinfunction "AY1_18") (pintype "tri_state"))
      (node (ref "U8") (pin "2") (pinfunction "I1_2") (pintype "input"))
    )
    (net (code "57") (name "/Cam_F1") (class "Default")
      (node (ref "R148") (pin "1") (pinfunction "1_1") (pintype "passive"))
      (node (ref "U3") (pin "14") (pinfunction "AY3_14") (pintype "tri_state"))
    )
    (net (code "58") (name "/Cam_F2") (class "Default")
      (node (ref "R171") (pin "1") (pinfunction "1_1") (pintype "passive"))
      (node (ref "U3") (pin "5") (pinfunction "BY3_5") (pintype "tri_state"))
    )
    (net (code "59") (name "/Cam_F4") (class "Default")
      (node (ref "R147") (pin "1") (pinfunction "1_1") (pintype "passive"))
      (node (ref "U3") (pin "16") (pinfunction "AY2_16") (pintype "tri_state"))
    )
    (net (code "60") (name "/Cam_F8") (class "Default")
      (node (ref "R170") (pin "1") (pinfunction "1_1") (pintype "passive"))
      (node (ref "U3") (pin "3") (pinfunction "BY4_3") (pintype "tri_state"))
    )
    (net (code "61") (name "/Cam_F16") (class "Default")
      (node (ref "R146") (pin "1") (pinfunction "1_1") (pintype "passive"))
      (node (ref "U3") (pin "18") (pinfunction "AY1_18") (pintype "tri_state"))
    )
    (net (code "62") (name "/Cam_L") (class "Default")
      (node (ref "R151") (pin "1") (pinfunction "1_1") (pintype "passive"))
      (node (ref "U9") (pin "4") (pinfunction "I0_4") (pintype "input"))
      (node (ref "U9") (pin "5") (pinfunction "I1_5") (pintype "input"))
    )
    (net (code "63") (name "/Cam_N") (class "Default")
      (node (ref "R150") (pin "1") (pinfunction "1_1") (pintype "passive"))
      (node (ref "U4") (pin "18") (pinfunction "AY1_18") (pintype "tri_state"))
    )
    (net (code "64") (name "/Cam_Q") (class "Default")
      (node (ref "R153") (pin "1") (pinfunction "1_1") (pintype "passive"))
      (node (ref "U9") (pin "12") (pinfunction "I0_12") (pintype "input"))
      (node (ref "U9") (pin "13") (pinfunction "I1_13") (pintype "input"))
    )
    (net (code "65") (name "/Cam_S1") (class "Default")
      (node (ref "R175") (pin "1") (pinfunction "1_1") (pintype "passive"))
      (node (ref "U4") (pin "14") (pinfunction "AY3_14") (pintype "tri_state"))
    )
    (net (code "66") (name "/Cam_S2") (class "Default")
      (node (ref "R176") (pin "1") (pinfunction "1_1") (pintype "passive"))
      (node (ref "U4") (pin "12") (pinfunction "AY4_12") (pintype "tri_state"))
    )
    (net (code "67") (name "/Cam_X") (class "Default")
      (node (ref "R152") (pin "1") (pinfunction "1_1") (pintype "passive"))
      (node (ref "U9") (pin "1") (pinfunction "I0_1") (pintype "input"))
      (node (ref "U9") (pin "2") (pinfunction "I1_2") (pintype "input"))
    )
    (net (code "68") (name "/RPortEn1") (class "Default")
      (node (ref "R194") (pin "2") (pinfunction "2_2") (pintype "passive"))
    )
    (net (code "69") (name "/RPortEn2") (class "Default")
      (node (ref "R211") (pin "2") (pinfunction "2_2") (pintype "passive"))
    )
    (net (code "70") (name "/RPort_En1") (class "Default")
      (node (ref "R194") (pin "1") (pinfunction "1_1") (pintype "passive"))
      (node (ref "U5") (pin "1") (pinfunction "I0_1") (pintype "input"))
      (node (ref "U5") (pin "12") (pinfunction "I0_12") (pintype "input"))
      (node (ref "U5") (pin "4") (pinfunction "I0_4") (pintype "input"))
      (node (ref "U5") (pin "9") (pinfunction "I0_9") (pintype "input"))
      (node (ref "U6") (pin "1") (pinfunction "I0_1") (pintype "input"))
      (node (ref "U6") (pin "12") (pinfunction "I0_12") (pintype "input"))
      (node (ref "U6") (pin "4") (pinfunction "I0_4") (pintype "input"))
      (node (ref "U6") (pin "9") (pinfunction "I0_9") (pintype "input"))
    )
    (net (code "71") (name "/RPort_En2") (class "Default")
      (node (ref "R211") (pin "1") (pinfunction "1_1") (pintype "passive"))
      (node (ref "U7") (pin "1") (pinfunction "I0_1") (pintype "input"))
      (node (ref "U7") (pin "12") (pinfunction "I0_12") (pintype "input"))
      (node (ref "U7") (pin "4") (pinfunction "I0_4") (pintype "input"))
      (node (ref "U7") (pin "9") (pinfunction "I0_9") (pintype "input"))
      (node (ref "U8") (pin "1") (pinfunction "I0_1") (pintype "input"))
      (node (ref "U8") (pin "12") (pinfunction "I0_12") (pintype "input"))
      (node (ref "U8") (pin "4") (pinfunction "I0_4") (pintype "input"))
      (node (ref "U8") (pin "9") (pinfunction "I0_9") (pintype "input"))
    )
    (net (code "72") (name "/WPortEn") (class "Default")
      (node (ref "R177") (pin "2") (pinfunction "2_2") (pintype "passive"))
    )
    (net (code "73") (name "/WPort_En") (class "Default")
      (node (ref "R177") (pin "1") (pinfunction "1_1") (pintype "passive"))
      (node (ref "U1") (pin "1") (pinfunction "~{OEA}_1") (pintype "input"))
      (node (ref "U1") (pin "19") (pinfunction "~{OEB}_19") (pintype "input"))
      (node (ref "U2") (pin "1") (pinfunction "~{OEA}_1") (pintype "input"))
      (node (ref "U2") (pin "19") (pinfunction "~{OEB}_19") (pintype "input"))
    )
    (net (code "74") (name "/nCamA1") (class "Default")
      (node (ref "R127") (pin "2") (pinfunction "2_2") (pintype "passive"))
      (node (ref "U4") (pin "4") (pinfunction "A2_4") (pintype "input"))
    )
    (net (code "75") (name "/nCamA2") (class "Default")
      (node (ref "R126") (pin "2") (pinfunction "2_2") (pintype "passive"))
      (node (ref "U3") (pin "11") (pinfunction "B1_11") (pintype "input"))
    )
    (net (code "76") (name "/nCamA4") (class "Default")
      (node (ref "R125") (pin "2") (pinfunction "2_2") (pintype "passive"))
      (node (ref "U3") (pin "8") (pinfunction "A4_8") (pintype "input"))
    )
    (net (code "77") (name "/nCamA8") (class "Default")
      (node (ref "R124") (pin "2") (pinfunction "2_2") (pintype "passive"))
      (node (ref "U3") (pin "13") (pinfunction "B2_13") (pintype "input"))
    )
    (net (code "78") (name "/nCamC") (class "Default")
      (node (ref "R54") (pin "1") (pinfunction "1_1") (pintype "passive"))
    )
    (net (code "79") (name "/nCamF1") (class "Default")
      (node (ref "R123") (pin "2") (pinfunction "2_2") (pintype "passive"))
      (node (ref "U3") (pin "6") (pinfunction "A3_6") (pintype "input"))
    )
    (net (code "80") (name "/nCamF2") (class "Default")
      (node (ref "R122") (pin "2") (pinfunction "2_2") (pintype "passive"))
      (node (ref "U3") (pin "15") (pinfunction "B3_15") (pintype "input"))
    )
    (net (code "81") (name "/nCamF4") (class "Default")
      (node (ref "R121") (pin "2") (pinfunction "2_2") (pintype "passive"))
      (node (ref "U3") (pin "4") (pinfunction "A2_4") (pintype "input"))
    )
    (net (code "82") (name "/nCamF8") (class "Default")
      (node (ref "R120") (pin "2") (pinfunction "2_2") (pintype "passive"))
      (node (ref "U3") (pin "17") (pinfunction "B4_17") (pintype "input"))
    )
    (net (code "83") (name "/nCamF16") (class "Default")
      (node (ref "R119") (pin "2") (pinfunction "2_2") (pintype "passive"))
      (node (ref "U3") (pin "2") (pinfunction "A1_2") (pintype "input"))
    )
    (net (code "84") (name "/nCamL") (class "Default")
      (node (ref "R56") (pin "1") (pinfunction "1_1") (pintype "passive"))
      (node (ref "U9") (pin "6") (pinfunction "~{O}_6") (pintype "open_collector"))
    )
    (net (code "85") (name "/nCamN") (class "Default")
      (node (ref "R55") (pin "1") (pinfunction "1_1") (pintype "passive"))
      (node (ref "U4") (pin "2") (pinfunction "A1_2") (pintype "input"))
    )
    (net (code "86") (name "/nCamQ") (class "Default")
      (node (ref "R129") (pin "2") (pinfunction "2_2") (pintype "passive"))
      (node (ref "U9") (pin "11") (pinfunction "~{O}_11") (pintype "open_collector"))
    )
    (net (code "87") (name "/nCamR1") (class "Default")
      (node (ref "R145") (pin "2") (pinfunction "2_2") (pintype "passive"))
      (node (ref "U5") (pin "8") (pinfunction "~{O}_8") (pintype "open_collector"))
      (node (ref "VD2") (pin "3") (pinfunction "3_3") (pintype "passive"))
    )
    (net (code "88") (name "/nCamR2") (class "Default")
      (node (ref "R118") (pin "1") (pinfunction "1_1") (pintype "passive"))
      (node (ref "U6") (pin "8") (pinfunction "~{O}_8") (pintype "open_collector"))
      (node (ref "VD1") (pin "3") (pinfunction "3_3") (pintype "passive"))
    )
    (net (code "89") (name "/nCamR3") (class "Default")
      (node (ref "R144") (pin "2") (pinfunction "2_2") (pintype "passive"))
      (node (ref "U5") (pin "6") (pinfunction "~{O}_6") (pintype "open_collector"))
    )
    (net (code "90") (name "/nCamR4") (class "Default")
      (node (ref "R80") (pin "1") (pinfunction "1_1") (pintype "passive"))
      (node (ref "U6") (pin "6") (pinfunction "~{O}_6") (pintype "open_collector"))
    )
    (net (code "91") (name "/nCamR5") (class "Default")
      (node (ref "R143") (pin "2") (pinfunction "2_2") (pintype "passive"))
      (node (ref "U5") (pin "11") (pinfunction "~{O}_11") (pintype "open_collector"))
    )
    (net (code "92") (name "/nCamR6") (class "Default")
      (node (ref "R79") (pin "1") (pinfunction "1_1") (pintype "passive"))
      (node (ref "U6") (pin "11") (pinfunction "~{O}_11") (pintype "open_collector"))
    )
    (net (code "93") (name "/nCamR7") (class "Default")
      (node (ref "R142") (pin "2") (pinfunction "2_2") (pintype "passive"))
      (node (ref "U5") (pin "3") (pinfunction "~{O}_3") (pintype "open_collector"))
    )
    (net (code "94") (name "/nCamR8") (class "Default")
      (node (ref "R78") (pin "1") (pinfunction "1_1") (pintype "passive"))
      (node (ref "U6") (pin "3") (pinfunction "~{O}_3") (pintype "open_collector"))
    )
    (net (code "95") (name "/nCamR9") (class "Default")
      (node (ref "R141") (pin "2") (pinfunction "2_2") (pintype "passive"))
      (node (ref "U7") (pin "8") (pinfunction "~{O}_8") (pintype "open_collector"))
    )
    (net (code "96") (name "/nCamR10") (class "Default")
      (node (ref "R72") (pin "1") (pinfunction "1_1") (pintype "passive"))
      (node (ref "U8") (pin "8") (pinfunction "~{O}_8") (pintype "open_collector"))
    )
    (net (code "97") (name "/nCamR11") (class "Default")
      (node (ref "R140") (pin "2") (pinfunction "2_2") (pintype "passive"))
      (node (ref "U7") (pin "6") (pinfunction "~{O}_6") (pintype "open_collector"))
    )
    (net (code "98") (name "/nCamR12") (class "Default")
      (node (ref "R71") (pin "1") (pinfunction "1_1") (pintype "passive"))
      (node (ref "U8") (pin "6") (pinfunction "~{O}_6") (pintype "open_collector"))
    )
    (net (code "99") (name "/nCamR13") (class "Default")
      (node (ref "R139") (pin "2") (pinfunction "2_2") (pintype "passive"))
      (node (ref "U7") (pin "11") (pinfunction "~{O}_11") (pintype "open_collector"))
    )
    (net (code "100") (name "/nCamR14") (class "Default")
      (node (ref "R70") (pin "1") (pinfunction "1_1") (pintype "passive"))
      (node (ref "U8") (pin "11") (pinfunction "~{O}_11") (pintype "open_collector"))
    )
    (net (code "101") (name "/nCamR15") (class "Default")
      (node (ref "R138") (pin "2") (pinfunction "2_2") (pintype "passive"))
      (node (ref "U7") (pin "3") (pinfunction "~{O}_3") (pintype "open_collector"))
    )
    (net (code "102") (name "/nCamR16") (class "Default")
      (node (ref "R67") (pin "1") (pinfunction "1_1") (pintype "passive"))
      (node (ref "U8") (pin "3") (pinfunction "~{O}_3") (pintype "open_collector"))
    )
    (net (code "103") (name "/nCamS1") (class "Default")
      (node (ref "R57") (pin "1") (pinfunction "1_1") (pintype "passive"))
      (node (ref "U4") (pin "6") (pinfunction "A3_6") (pintype "input"))
    )
    (net (code "104") (name "/nCamS2") (class "Default")
      (node (ref "R58") (pin "1") (pinfunction "1_1") (pintype "passive"))
      (node (ref "U4") (pin "8") (pinfunction "A4_8") (pintype "input"))
    )
    (net (code "105") (name "/nCamW1") (class "Default")
      (node (ref "R137") (pin "2") (pinfunction "2_2") (pintype "passive"))
      (node (ref "U1") (pin "11") (pinfunction "B1_11") (pintype "input"))
    )
    (net (code "106") (name "/nCamW2") (class "Default")
      (node (ref "R66") (pin "1") (pinfunction "1_1") (pintype "passive"))
      (node (ref "U2") (pin "11") (pinfunction "B1_11") (pintype "input"))
    )
    (net (code "107") (name "/nCamW3") (class "Default")
      (node (ref "R136") (pin "2") (pinfunction "2_2") (pintype "passive"))
      (node (ref "U1") (pin "8") (pinfunction "A4_8") (pintype "input"))
    )
    (net (code "108") (name "/nCamW4") (class "Default")
      (node (ref "R65") (pin "1") (pinfunction "1_1") (pintype "passive"))
      (node (ref "U2") (pin "8") (pinfunction "A4_8") (pintype "input"))
    )
    (net (code "109") (name "/nCamW5") (class "Default")
      (node (ref "R135") (pin "2") (pinfunction "2_2") (pintype "passive"))
      (node (ref "U1") (pin "13") (pinfunction "B2_13") (pintype "input"))
    )
    (net (code "110") (name "/nCamW6") (class "Default")
      (node (ref "R64") (pin "1") (pinfunction "1_1") (pintype "passive"))
      (node (ref "U2") (pin "13") (pinfunction "B2_13") (pintype "input"))
    )
    (net (code "111") (name "/nCamW7") (class "Default")
      (node (ref "R134") (pin "2") (pinfunction "2_2") (pintype "passive"))
      (node (ref "U1") (pin "6") (pinfunction "A3_6") (pintype "input"))
    )
    (net (code "112") (name "/nCamW8") (class "Default")
      (node (ref "R63") (pin "1") (pinfunction "1_1") (pintype "passive"))
      (node (ref "U2") (pin "6") (pinfunction "A3_6") (pintype "input"))
    )
    (net (code "113") (name "/nCamW9") (class "Default")
      (node (ref "R133") (pin "2") (pinfunction "2_2") (pintype "passive"))
      (node (ref "U1") (pin "15") (pinfunction "B3_15") (pintype "input"))
    )
    (net (code "114") (name "/nCamW10") (class "Default")
      (node (ref "R62") (pin "1") (pinfunction "1_1") (pintype "passive"))
      (node (ref "U2") (pin "15") (pinfunction "B3_15") (pintype "input"))
    )
    (net (code "115") (name "/nCamW11") (class "Default")
      (node (ref "R132") (pin "2") (pinfunction "2_2") (pintype "passive"))
      (node (ref "U1") (pin "4") (pinfunction "A2_4") (pintype "input"))
    )
    (net (code "116") (name "/nCamW12") (class "Default")
      (node (ref "R61") (pin "1") (pinfunction "1_1") (pintype "passive"))
      (node (ref "U2") (pin "4") (pinfunction "A2_4") (pintype "input"))
    )
    (net (code "117") (name "/nCamW13") (class "Default")
      (node (ref "R131") (pin "2") (pinfunction "2_2") (pintype "passive"))
      (node (ref "U1") (pin "17") (pinfunction "B4_17") (pintype "input"))
    )
    (net (code "118") (name "/nCamW14") (class "Default")
      (node (ref "R60") (pin "1") (pinfunction "1_1") (pintype "passive"))
      (node (ref "U2") (pin "17") (pinfunction "B4_17") (pintype "input"))
    )
    (net (code "119") (name "/nCamW15") (class "Default")
      (node (ref "R130") (pin "2") (pinfunction "2_2") (pintype "passive"))
      (node (ref "U1") (pin "2") (pinfunction "A1_2") (pintype "input"))
    )
    (net (code "120") (name "/nCamW16") (class "Default")
      (node (ref "R59") (pin "1") (pinfunction "1_1") (pintype "passive"))
      (node (ref "U2") (pin "2") (pinfunction "A1_2") (pintype "input"))
    )
    (net (code "121") (name "/nCamX") (class "Default")
      (node (ref "R1") (pin "1") (pinfunction "1_1") (pintype "passive"))
      (node (ref "U9") (pin "3") (pinfunction "~{O}_3") (pintype "open_collector"))
    )
    (net (code "122") (name "/nCamZ") (class "Default")
      (node (ref "R128") (pin "2") (pinfunction "2_2") (pintype "passive"))
    )
    (net (code "123") (name "Cam-6v") (class "Default")
      (node (ref "J1") (pin "B38") (pinfunction "-6_B38") (pintype "passive"))
      (node (ref "L1") (pin "1") (pinfunction "1_1") (pintype "passive"))
    )
    (net (code "124") (name "GND") (class "Default")
      (node (ref "C1") (pin "+") (pinfunction "+_+") (pintype "passive"))
      (node (ref "C2") (pin "2") (pinfunction "2_2") (pintype "passive"))
      (node (ref "C3") (pin "-") (pinfunction "-_-") (pintype "passive"))
      (node (ref "C4") (pin "2") (pinfunction "2_2") (pintype "passive"))
      (node (ref "C5") (pin "2") (pinfunction "2_2") (pintype "passive"))
      (node (ref "C6") (pin "2") (pinfunction "2_2") (pintype "passive"))
      (node (ref "C7") (pin "2") (pinfunction "2_2") (pintype "passive"))
      (node (ref "C88") (pin "+") (pinfunction "+_+") (pintype "passive"))
      (node (ref "J1") (pin "A43") (pinfunction "GND_A43") (pintype "passive"))
      (node (ref "J1") (pin "B43") (pinfunction "GND_B43") (pintype "passive"))
      (node (ref "U1") (pin "10") (pinfunction "GND_10") (pintype "power_in"))
      (node (ref "U2") (pin "10") (pinfunction "GND_10") (pintype "power_in"))
      (node (ref "U3") (pin "1") (pinfunction "~{OEA}_1") (pintype "input"))
      (node (ref "U3") (pin "10") (pinfunction "GND_10") (pintype "power_in"))
      (node (ref "U3") (pin "19") (pinfunction "~{OEB}_19") (pintype "input"))
      (node (ref "U4") (pin "1") (pinfunction "~{OEA}_1") (pintype "input"))
      (node (ref "U4") (pin "10") (pinfunction "GND_10") (pintype "power_in"))
      (node (ref "U4") (pin "19") (pinfunction "~{OEB}_19") (pintype "input"))
      (node (ref "VD1") (pin "1") (pinfunction "1_1") (pintype "passive"))
      (node (ref "VD2") (pin "1") (pinfunction "1_1") (pintype "passive"))
    )
    (net (code "125") (name "Net-(J1-A1)") (class "Default")
      (node (ref "J1") (pin "B10") (pinfunction "A1_B10") (pintype "passive"))
      (node (ref "R127") (pin "1") (pinfunction "1_1") (pintype "passive"))
    )
    (net (code "126") (name "Net-(J1-A2)") (class "Default")
      (node (ref "J1") (pin "B9") (pinfunction "A2_B9") (pintype "passive"))
      (node (ref "R126") (pin "1") (pinfunction "1_1") (pintype "passive"))
    )
    (net (code "127") (name "Net-(J1-A4)") (class "Default")
      (node (ref "J1") (pin "B8") (pinfunction "A4_B8") (pintype "passive"))
      (node (ref "R125") (pin "1") (pinfunction "1_1") (pintype "passive"))
    )
    (net (code "128") (name "Net-(J1-A8)") (class "Default")
      (node (ref "J1") (pin "B7") (pinfunction "A8_B7") (pintype "passive"))
      (node (ref "R124") (pin "1") (pinfunction "1_1") (pintype "passive"))
    )
    (net (code "129") (name "Net-(J1-C)") (class "Default")
      (node (ref "J1") (pin "A8") (pinfunction "C_A8") (pintype "passive"))
      (node (ref "R54") (pin "2") (pinfunction "2_2") (pintype "passive"))
    )
    (net (code "130") (name "Net-(J1-F1)") (class "Default")
      (node (ref "J1") (pin "B6") (pinfunction "F1_B6") (pintype "passive"))
      (node (ref "R123") (pin "1") (pinfunction "1_1") (pintype "passive"))
    )
    (net (code "131") (name "Net-(J1-F2)") (class "Default")
      (node (ref "J1") (pin "B5") (pinfunction "F2_B5") (pintype "passive"))
      (node (ref "R122") (pin "1") (pinfunction "1_1") (pintype "passive"))
    )
    (net (code "132") (name "Net-(J1-F4)") (class "Default")
      (node (ref "J1") (pin "B4") (pinfunction "F4_B4") (pintype "passive"))
      (node (ref "R121") (pin "1") (pinfunction "1_1") (pintype "passive"))
    )
    (net (code "133") (name "Net-(J1-F8)") (class "Default")
      (node (ref "J1") (pin "B3") (pinfunction "F8_B3") (pintype "passive"))
      (node (ref "R120") (pin "1") (pinfunction "1_1") (pintype "passive"))
    )
    (net (code "134") (name "Net-(J1-F16)") (class "Default")
      (node (ref "J1") (pin "B2") (pinfunction "F16_B2") (pintype "passive"))
      (node (ref "R119") (pin "1") (pinfunction "1_1") (pintype "passive"))
    )
    (net (code "135") (name "Net-(J1-L)") (class "Default")
      (node (ref "J1") (pin "A10") (pinfunction "L_A10") (pintype "passive"))
      (node (ref "R56") (pin "2") (pinfunction "2_2") (pintype "passive"))
    )
    (net (code "136") (name "Net-(J1-N)") (class "Default")
      (node (ref "J1") (pin "A9") (pinfunction "N_A9") (pintype "passive"))
      (node (ref "R55") (pin "2") (pinfunction "2_2") (pintype "passive"))
    )
    (net (code "137") (name "Net-(J1-Q)") (class "Default")
      (node (ref "J1") (pin "B12") (pinfunction "Q_B12") (pintype "passive"))
      (node (ref "R129") (pin "1") (pinfunction "1_1") (pintype "passive"))
    )
    (net (code "138") (name "Net-(J1-R1)") (class "Default")
      (node (ref "J1") (pin "B36") (pinfunction "R1_B36") (pintype "passive"))
      (node (ref "R145") (pin "1") (pinfunction "1_1") (pintype "passive"))
    )
    (net (code "139") (name "Net-(J1-R2)") (class "Default")
      (node (ref "J1") (pin "A36") (pinfunction "R2_A36") (pintype "passive"))
      (node (ref "R118") (pin "2") (pinfunction "2_2") (pintype "passive"))
    )
    (net (code "140") (name "Net-(J1-R3)") (class "Default")
      (node (ref "J1") (pin "B35") (pinfunction "R3_B35") (pintype "passive"))
      (node (ref "R144") (pin "1") (pinfunction "1_1") (pintype "passive"))
    )
    (net (code "141") (name "Net-(J1-R4)") (class "Default")
      (node (ref "J1") (pin "A35") (pinfunction "R4_A35") (pintype "passive"))
      (node (ref "R80") (pin "2") (pinfunction "2_2") (pintype "passive"))
    )
    (net (code "142") (name "Net-(J1-R5)") (class "Default")
      (node (ref "J1") (pin "B34") (pinfunction "R5_B34") (pintype "passive"))
      (node (ref "R143") (pin "1") (pinfunction "1_1") (pintype "passive"))
    )
    (net (code "143") (name "Net-(J1-R6)") (class "Default")
      (node (ref "J1") (pin "A34") (pinfunction "R6_A34") (pintype "passive"))
      (node (ref "R79") (pin "2") (pinfunction "2_2") (pintype "passive"))
    )
    (net (code "144") (name "Net-(J1-R7)") (class "Default")
      (node (ref "J1") (pin "B33") (pinfunction "R7_B33") (pintype "passive"))
      (node (ref "R142") (pin "1") (pinfunction "1_1") (pintype "passive"))
    )
    (net (code "145") (name "Net-(J1-R8)") (class "Default")
      (node (ref "J1") (pin "A33") (pinfunction "R8_A33") (pintype "passive"))
      (node (ref "R78") (pin "2") (pinfunction "2_2") (pintype "passive"))
    )
    (net (code "146") (name "Net-(J1-R9)") (class "Default")
      (node (ref "J1") (pin "B32") (pinfunction "R9_B32") (pintype "passive"))
      (node (ref "R141") (pin "1") (pinfunction "1_1") (pintype "passive"))
    )
    (net (code "147") (name "Net-(J1-R10)") (class "Default")
      (node (ref "J1") (pin "A32") (pinfunction "R10_A32") (pintype "passive"))
      (node (ref "R72") (pin "2") (pinfunction "2_2") (pintype "passive"))
    )
    (net (code "148") (name "Net-(J1-R11)") (class "Default")
      (node (ref "J1") (pin "B31") (pinfunction "R11_B31") (pintype "passive"))
      (node (ref "R140") (pin "1") (pinfunction "1_1") (pintype "passive"))
    )
    (net (code "149") (name "Net-(J1-R12)") (class "Default")
      (node (ref "J1") (pin "A31") (pinfunction "R12_A31") (pintype "passive"))
      (node (ref "R71") (pin "2") (pinfunction "2_2") (pintype "passive"))
    )
    (net (code "150") (name "Net-(J1-R13)") (class "Default")
      (node (ref "J1") (pin "B30") (pinfunction "R13_B30") (pintype "passive"))
      (node (ref "R139") (pin "1") (pinfunction "1_1") (pintype "passive"))
    )
    (net (code "151") (name "Net-(J1-R14)") (class "Default")
      (node (ref "J1") (pin "A30") (pinfunction "R14_A30") (pintype "passive"))
      (node (ref "R70") (pin "2") (pinfunction "2_2") (pintype "passive"))
    )
    (net (code "152") (name "Net-(J1-R15)") (class "Default")
      (node (ref "J1") (pin "B29") (pinfunction "R15_B29") (pintype "passive"))
      (node (ref "R138") (pin "1") (pinfunction "1_1") (pintype "passive"))
    )
    (net (code "153") (name "Net-(J1-R16)") (class "Default")
      (node (ref "J1") (pin "A29") (pinfunction "R16_A29") (pintype "passive"))
      (node (ref "R67") (pin "2") (pinfunction "2_2") (pintype "passive"))
    )
    (net (code "154") (name "Net-(J1-S1)") (class "Default")
      (node (ref "J1") (pin "A11") (pinfunction "S1_A11") (pintype "passive"))
      (node (ref "R57") (pin "2") (pinfunction "2_2") (pintype "passive"))
    )
    (net (code "155") (name "Net-(J1-S2)") (class "Default")
      (node (ref "J1") (pin "A12") (pinfunction "S2_A12") (pintype "passive"))
      (node (ref "R58") (pin "2") (pinfunction "2_2") (pintype "passive"))
    )
    (net (code "156") (name "Net-(J1-W1)") (class "Default")
      (node (ref "J1") (pin "B24") (pinfunction "W1_B24") (pintype "passive"))
      (node (ref "R137") (pin "1") (pinfunction "1_1") (pintype "passive"))
    )
    (net (code "157") (name "Net-(J1-W2)") (class "Default")
      (node (ref "J1") (pin "A24") (pinfunction "W2_A24") (pintype "passive"))
      (node (ref "R66") (pin "2") (pinfunction "2_2") (pintype "passive"))
    )
    (net (code "158") (name "Net-(J1-W3)") (class "Default")
      (node (ref "J1") (pin "B23") (pinfunction "W3_B23") (pintype "passive"))
      (node (ref "R136") (pin "1") (pinfunction "1_1") (pintype "passive"))
    )
    (net (code "159") (name "Net-(J1-W4)") (class "Default")
      (node (ref "J1") (pin "A23") (pinfunction "W4_A23") (pintype "passive"))
      (node (ref "R65") (pin "2") (pinfunction "2_2") (pintype "passive"))
    )
    (net (code "160") (name "Net-(J1-W5)") (class "Default")
      (node (ref "J1") (pin "B22") (pinfunction "W5_B22") (pintype "passive"))
      (node (ref "R135") (pin "1") (pinfunction "1_1") (pintype "passive"))
    )
    (net (code "161") (name "Net-(J1-W6)") (class "Default")
      (node (ref "J1") (pin "A22") (pinfunction "W6_A22") (pintype "passive"))
      (node (ref "R64") (pin "2") (pinfunction "2_2") (pintype "passive"))
    )
    (net (code "162") (name "Net-(J1-W7)") (class "Default")
      (node (ref "J1") (pin "B21") (pinfunction "W7_B21") (pintype "passive"))
      (node (ref "R134") (pin "1") (pinfunction "1_1") (pintype "passive"))
    )
    (net (code "163") (name "Net-(J1-W8)") (class "Default")
      (node (ref "J1") (pin "A21") (pinfunction "W8_A21") (pintype "passive"))
      (node (ref "R63") (pin "2") (pinfunction "2_2") (pintype "passive"))
    )
    (net (code "164") (name "Net-(J1-W9)") (class "Default")
      (node (ref "J1") (pin "B20") (pinfunction "W9_B20") (pintype "passive"))
      (node (ref "R133") (pin "1") (pinfunction "1_1") (pintype "passive"))
    )
    (net (code "165") (name "Net-(J1-W10)") (class "Default")
      (node (ref "J1") (pin "A20") (pinfunction "W10_A20") (pintype "passive"))
      (node (ref "R62") (pin "2") (pinfunction "2_2") (pintype "passive"))
    )
    (net (code "166") (name "Net-(J1-W11)") (class "Default")
      (node (ref "J1") (pin "B19") (pinfunction "W11_B19") (pintype "passive"))
      (node (ref "R132") (pin "1") (pinfunction "1_1") (pintype "passive"))
    )
    (net (code "167") (name "Net-(J1-W12)") (class "Default")
      (node (ref "J1") (pin "A19") (pinfunction "W12_A19") (pintype "passive"))
      (node (ref "R61") (pin "2") (pinfunction "2_2") (pintype "passive"))
    )
    (net (code "168") (name "Net-(J1-W13)") (class "Default")
      (node (ref "J1") (pin "B18") (pinfunction "W13_B18") (pintype "passive"))
      (node (ref "R131") (pin "1") (pinfunction "1_1") (pintype "passive"))
    )
    (net (code "169") (name "Net-(J1-W14)") (class "Default")
      (node (ref "J1") (pin "A18") (pinfunction "W14_A18") (pintype "passive"))
      (node (ref "R60") (pin "2") (pinfunction "2_2") (pintype "passive"))
    )
    (net (code "170") (name "Net-(J1-W15)") (class "Default")
      (node (ref "J1") (pin "B17") (pinfunction "W15_B17") (pintype "passive"))
      (node (ref "R130") (pin "1") (pinfunction "1_1") (pintype "passive"))
    )
    (net (code "171") (name "Net-(J1-W16)") (class "Default")
      (node (ref "J1") (pin "A17") (pinfunction "W16_A17") (pintype "passive"))
      (node (ref "R59") (pin "2") (pinfunction "2_2") (pintype "passive"))
    )
    (net (code "172") (name "Net-(J1-X)") (class "Default")
      (node (ref "J1") (pin "A6") (pinfunction "X_A6") (pintype "passive"))
      (node (ref "R1") (pin "2") (pinfunction "2_2") (pintype "passive"))
    )
    (net (code "173") (name "Net-(J1-Z)") (class "Default")
      (node (ref "J1") (pin "B11") (pinfunction "Z_B11") (pintype "passive"))
      (node (ref "R128") (pin "1") (pinfunction "1_1") (pintype "passive"))
    )
    (net (code "174") (name "Net-(R178-Pad2)") (class "Default")
      (node (ref "R178") (pin "2") (pinfunction "2_2") (pintype "passive"))
      (node (ref "R195") (pin "1") (pinfunction "1_1") (pintype "passive"))
    )
    (net (code "175") (name "Net-(R179-Pad2)") (class "Default")
      (node (ref "R179") (pin "2") (pinfunction "2_2") (pintype "passive"))
      (node (ref "R196") (pin "1") (pinfunction "1_1") (pintype "passive"))
    )
    (net (code "176") (name "Net-(R180-Pad2)") (class "Default")
      (node (ref "R180") (pin "2") (pinfunction "2_2") (pintype "passive"))
      (node (ref "R197") (pin "1") (pinfunction "1_1") (pintype "passive"))
    )
    (net (code "177") (name "Net-(R181-Pad2)") (class "Default")
      (node (ref "R181") (pin "2") (pinfunction "2_2") (pintype "passive"))
      (node (ref "R198") (pin "1") (pinfunction "1_1") (pintype "passive"))
    )
    (net (code "178") (name "Net-(R182-Pad2)") (class "Default")
      (node (ref "R182") (pin "2") (pinfunction "2_2") (pintype "passive"))
      (node (ref "R199") (pin "1") (pinfunction "1_1") (pintype "passive"))
    )
    (net (code "179") (name "Net-(R183-Pad2)") (class "Default")
      (node (ref "R183") (pin "2") (pinfunction "2_2") (pintype "passive"))
      (node (ref "R200") (pin "1") (pinfunction "1_1") (pintype "passive"))
    )
    (net (code "180") (name "Net-(R184-Pad2)") (class "Default")
      (node (ref "R184") (pin "2") (pinfunction "2_2") (pintype "passive"))
      (node (ref "R201") (pin "1") (pinfunction "1_1") (pintype "passive"))
    )
    (net (code "181") (name "Net-(R185-Pad2)") (class "Default")
      (node (ref "R185") (pin "2") (pinfunction "2_2") (pintype "passive"))
      (node (ref "R202") (pin "1") (pinfunction "1_1") (pintype "passive"))
    )
    (net (code "182") (name "Net-(R186-Pad2)") (class "Default")
      (node (ref "R186") (pin "2") (pinfunction "2_2") (pintype "passive"))
      (node (ref "R203") (pin "1") (pinfunction "1_1") (pintype "passive"))
    )
    (net (code "183") (name "Net-(R187-Pad2)") (class "Default")
      (node (ref "R187") (pin "2") (pinfunction "2_2") (pintype "passive"))
      (node (ref "R204") (pin "1") (pinfunction "1_1") (pintype "passive"))
    )
    (net (code "184") (name "Net-(R188-Pad2)") (class "Default")
      (node (ref "R188") (pin "2") (pinfunction "2_2") (pintype "passive"))
      (node (ref "R205") (pin "1") (pinfunction "1_1") (pintype "passive"))
    )
    (net (code "185") (name "Net-(R189-Pad2)") (class "Default")
      (node (ref "R189") (pin "2") (pinfunction "2_2") (pintype "passive"))
      (node (ref "R206") (pin "1") (pinfunction "1_1") (pintype "passive"))
    )
    (net (code "186") (name "Net-(R190-Pad2)") (class "Default")
      (node (ref "R190") (pin "2") (pinfunction "2_2") (pintype "passive"))
      (node (ref "R207") (pin "1") (pinfunction "1_1") (pintype "passive"))
    )
    (net (code "187") (name "Net-(R191-Pad2)") (class "Default")
      (node (ref "R191") (pin "2") (pinfunction "2_2") (pintype "passive"))
      (node (ref "R208") (pin "1") (pinfunction "1_1") (pintype "passive"))
    )
    (net (code "188") (name "Net-(R192-Pad2)") (class "Default")
      (node (ref "R192") (pin "2") (pinfunction "2_2") (pintype "passive"))
      (node (ref "R209") (pin "1") (pinfunction "1_1") (pintype "passive"))
    )
    (net (code "189") (name "Net-(R193-Pad2)") (class "Default")
      (node (ref "R193") (pin "2") (pinfunction "2_2") (pintype "passive"))
      (node (ref "R210") (pin "1") (pinfunction "1_1") (pintype "passive"))
    )
    (net (code "190") (name "Net-(VD3-PadCATH)") (class "Default")
      (node (ref "VD3") (pin "CATH") (pinfunction "CATH_CATH") (pintype "passive"))
      (node (ref "VD4") (pin "ANOD") (pinfunction "ANOD_ANOD") (pintype "passive"))
    )
    (net (code "191") (name "VCC") (class "Default")
      (node (ref "C3") (pin "+") (pinfunction "+_+") (pintype "passive"))
      (node (ref "C4") (pin "1") (pinfunction "1_1") (pintype "passive"))
      (node (ref "C5") (pin "1") (pinfunction "1_1") (pintype "passive"))
      (node (ref "C6") (pin "1") (pinfunction "1_1") (pintype "passive"))
      (node (ref "C7") (pin "1") (pinfunction "1_1") (pintype "passive"))
      (node (ref "VD4") (pin "CATH") (pinfunction "CATH_CATH") (pintype "passive"))
    )
    (net (code "192") (name "unconnected-(J1-+12-PadA41)") (class "Default")
      (node (ref "J1") (pin "A41") (pinfunction "+12_A41") (pintype "passive"))
    )
    (net (code "193") (name "unconnected-(J1-+24-PadB41)") (class "Default")
      (node (ref "J1") (pin "B41") (pinfunction "+24_B41") (pintype "passive"))
    )
    (net (code "194") (name "unconnected-(J1-+200-PadA38)") (class "Default")
      (node (ref "J1") (pin "A38") (pinfunction "+200_A38") (pintype "passive"))
    )
    (net (code "195") (name "unconnected-(J1--12-PadA37)") (class "Default")
      (node (ref "J1") (pin "A37") (pinfunction "-12_A37") (pintype "passive"))
    )
    (net (code "196") (name "unconnected-(J1--24-PadB37)") (class "Default")
      (node (ref "J1") (pin "B37") (pinfunction "-24_B37") (pintype "passive"))
    )
    (net (code "197") (name "unconnected-(J1-ACL-PadA39)") (class "Default")
      (node (ref "J1") (pin "A39") (pinfunction "ACL_A39") (pintype "passive"))
    )
    (net (code "198") (name "unconnected-(J1-ACN-PadB39)") (class "Default")
      (node (ref "J1") (pin "B39") (pinfunction "ACN_B39") (pintype "passive"))
    )
    (net (code "199") (name "unconnected-(J1-B-PadB1)") (class "Default")
      (node (ref "J1") (pin "B1") (pinfunction "B_B1") (pintype "passive"))
    )
    (net (code "200") (name "unconnected-(J1-E-PadB40)") (class "Default")
      (node (ref "J1") (pin "B40") (pinfunction "E_B40") (pintype "passive"))
    )
    (net (code "201") (name "unconnected-(J1-I-PadA7)") (class "Default")
      (node (ref "J1") (pin "A7") (pinfunction "I_A7") (pintype "passive"))
    )
    (net (code "202") (name "unconnected-(J1-P1-PadA1)") (class "Default")
      (node (ref "J1") (pin "A1") (pinfunction "P1_A1") (pintype "passive"))
    )
    (net (code "203") (name "unconnected-(J1-P2-PadA2)") (class "Default")
      (node (ref "J1") (pin "A2") (pinfunction "P2_A2") (pintype "passive"))
    )
    (net (code "204") (name "unconnected-(J1-P3-PadA3)") (class "Default")
      (node (ref "J1") (pin "A3") (pinfunction "P3_A3") (pintype "passive"))
    )
    (net (code "205") (name "unconnected-(J1-P4-PadA4)") (class "Default")
      (node (ref "J1") (pin "A4") (pinfunction "P4_A4") (pintype "passive"))
    )
    (net (code "206") (name "unconnected-(J1-P5-PadA5)") (class "Default")
      (node (ref "J1") (pin "A5") (pinfunction "P5_A5") (pintype "passive"))
    )
    (net (code "207") (name "unconnected-(J1-R17-PadB28)") (class "Default")
      (node (ref "J1") (pin "B28") (pinfunction "R17_B28") (pintype "passive"))
    )
    (net (code "208") (name "unconnected-(J1-R18-PadA28)") (class "Default")
      (node (ref "J1") (pin "A28") (pinfunction "R18_A28") (pintype "passive"))
    )
    (net (code "209") (name "unconnected-(J1-R19-PadB27)") (class "Default")
      (node (ref "J1") (pin "B27") (pinfunction "R19_B27") (pintype "passive"))
    )
    (net (code "210") (name "unconnected-(J1-R20-PadA27)") (class "Default")
      (node (ref "J1") (pin "A27") (pinfunction "R20_A27") (pintype "passive"))
    )
    (net (code "211") (name "unconnected-(J1-R21-PadB26)") (class "Default")
      (node (ref "J1") (pin "B26") (pinfunction "R21_B26") (pintype "passive"))
    )
    (net (code "212") (name "unconnected-(J1-R22-PadA26)") (class "Default")
      (node (ref "J1") (pin "A26") (pinfunction "R22_A26") (pintype "passive"))
    )
    (net (code "213") (name "unconnected-(J1-R23-PadB25)") (class "Default")
      (node (ref "J1") (pin "B25") (pinfunction "R23_B25") (pintype "passive"))
    )
    (net (code "214") (name "unconnected-(J1-R24-PadA25)") (class "Default")
      (node (ref "J1") (pin "A25") (pinfunction "R24_A25") (pintype "passive"))
    )
    (net (code "215") (name "unconnected-(J1-W17-PadB16)") (class "Default")
      (node (ref "J1") (pin "B16") (pinfunction "W17_B16") (pintype "passive"))
    )
    (net (code "216") (name "unconnected-(J1-W18-PadA16)") (class "Default")
      (node (ref "J1") (pin "A16") (pinfunction "W18_A16") (pintype "passive"))
    )
    (net (code "217") (name "unconnected-(J1-W19-PadB15)") (class "Default")
      (node (ref "J1") (pin "B15") (pinfunction "W19_B15") (pintype "passive"))
    )
    (net (code "218") (name "unconnected-(J1-W20-PadA15)") (class "Default")
      (node (ref "J1") (pin "A15") (pinfunction "W20_A15") (pintype "passive"))
    )
    (net (code "219") (name "unconnected-(J1-W21-PadB14)") (class "Default")
      (node (ref "J1") (pin "B14") (pinfunction "W21_B14") (pintype "passive"))
    )
    (net (code "220") (name "unconnected-(J1-W22-PadA14)") (class "Default")
      (node (ref "J1") (pin "A14") (pinfunction "W22_A14") (pintype "passive"))
    )
    (net (code "221") (name "unconnected-(J1-W23-PadB13)") (class "Default")
      (node (ref "J1") (pin "B13") (pinfunction "W23_B13") (pintype "passive"))
    )
    (net (code "222") (name "unconnected-(J1-W24-PadA13)") (class "Default")
      (node (ref "J1") (pin "A13") (pinfunction "W24_A13") (pintype "passive"))
    )
    (net (code "223") (name "unconnected-(J1-Y1-PadA40)") (class "Default")
      (node (ref "J1") (pin "A40") (pinfunction "Y1_A40") (pintype "passive"))
    )
    (net (code "224") (name "unconnected-(J1-Y2-PadA42)") (class "Default")
      (node (ref "J1") (pin "A42") (pinfunction "Y2_A42") (pintype "passive"))
    )
    (net (code "225") (name "unconnected-(U4-B1-Pad11)") (class "Default")
      (node (ref "U4") (pin "11") (pinfunction "B1_11") (pintype "input"))
    )
    (net (code "226") (name "unconnected-(U4-B2-Pad13)") (class "Default")
      (node (ref "U4") (pin "13") (pinfunction "B2_13") (pintype "input"))
    )
    (net (code "227") (name "unconnected-(U4-B3-Pad15)") (class "Default")
      (node (ref "U4") (pin "15") (pinfunction "B3_15") (pintype "input"))
    )
    (net (code "228") (name "unconnected-(U4-B4-Pad17)") (class "Default")
      (node (ref "U4") (pin "17") (pinfunction "B4_17") (pintype "input"))
    )
    (net (code "229") (name "unconnected-(U4-BY1-Pad9)") (class "Default")
      (node (ref "U4") (pin "9") (pinfunction "BY1_9") (pintype "tri_state"))
    )
    (net (code "230") (name "unconnected-(U4-BY2-Pad7)") (class "Default")
      (node (ref "U4") (pin "7") (pinfunction "BY2_7") (pintype "tri_state"))
    )
    (net (code "231") (name "unconnected-(U4-BY3-Pad5)") (class "Default")
      (node (ref "U4") (pin "5") (pinfunction "BY3_5") (pintype "tri_state"))
    )
    (net (code "232") (name "unconnected-(U4-BY4-Pad3)") (class "Default")
      (node (ref "U4") (pin "3") (pinfunction "BY4_3") (pintype "tri_state"))
    )
    (net (code "233") (name "unconnected-(VD1-Pad2)") (class "Default")
      (node (ref "VD1") (pin "2") (pinfunction "2_2") (pintype "passive"))
    )
    (net (code "234") (name "unconnected-(VD2-Pad2)") (class "Default")
      (node (ref "VD2") (pin "2") (pinfunction "2_2") (pintype "passive"))
    )
  )
)
